# untitled.net
KiCad netlist of a schematic drawn in EAGLE
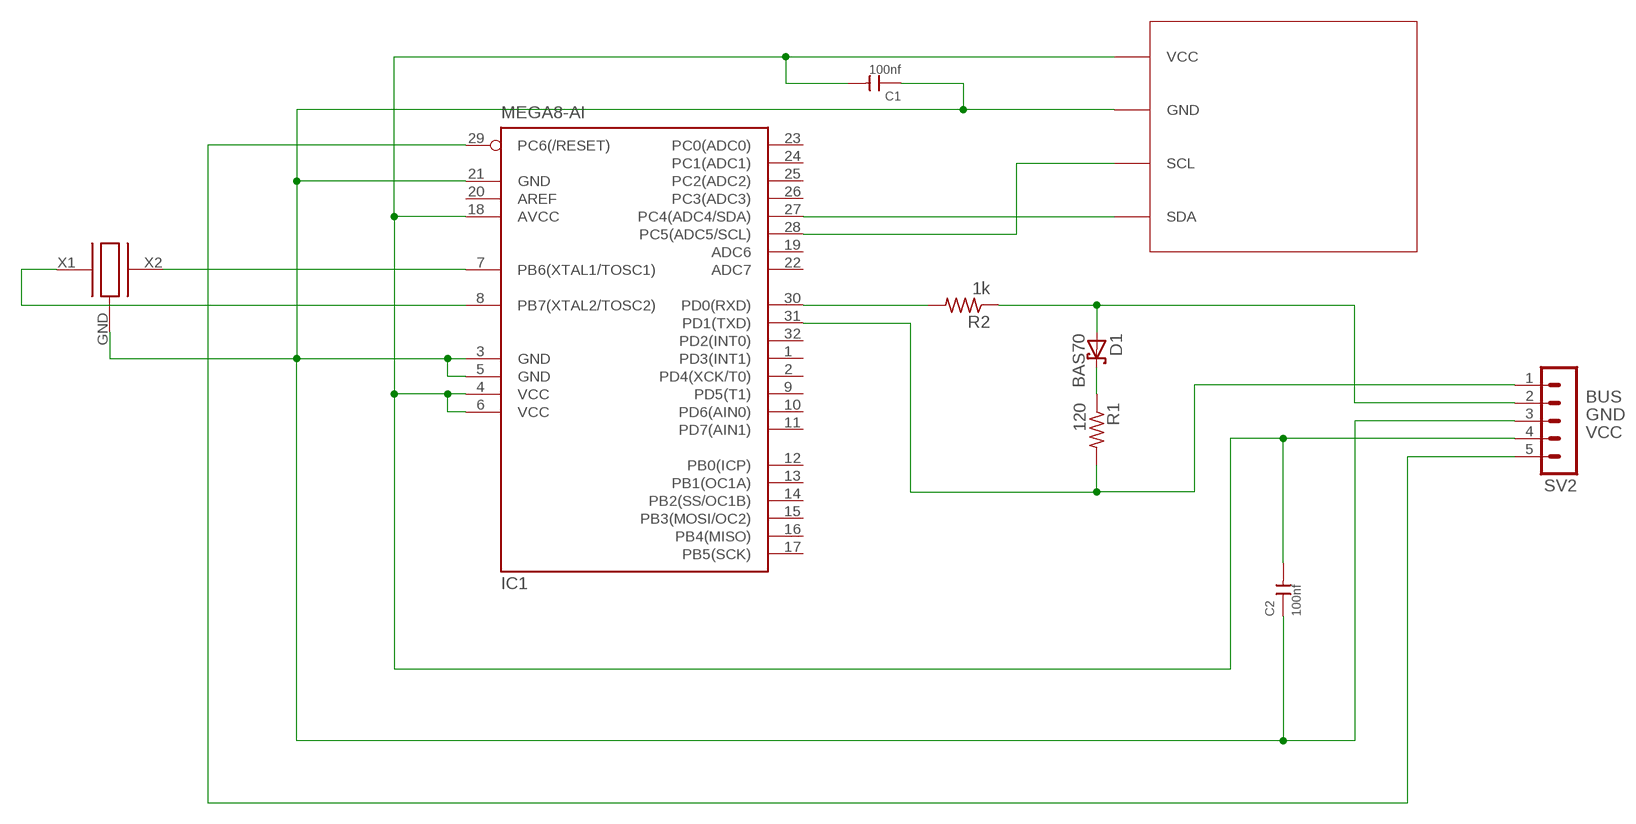
[diagram p0: schematic, sheet 1]

(export (version "E")
  (design (tool "Eeschema 10.0.6"))
  (components
    (comp (ref "C1")
      (value "100nf")
      (footprint "eagle-import:C0805")
      (fields (field (name "MPN") "CC0805JRX7R9BB103"))
      (libsource (lib "eagle-import") (part "CERAMIC-10NF-50V-5%-X7R(0805)"))
    )
    (comp (ref "C2")
      (value "100nf")
      (footprint "eagle-import:C0805")
      (fields (field (name "MPN") "CC0805JRX7R9BB103"))
      (libsource (lib "eagle-import") (part "CERAMIC-10NF-50V-5%-X7R(0805)"))
    )
    (comp (ref "D1")
      (value "BAS70")
      (footprint "eagle-import:SOT23")
      (libsource (lib "eagle-import") (part "BAS70"))
    )
    (comp (ref "IC1")
      (value "MEGA8-AI")
      (footprint "eagle-import:TQFP32-08")
      (fields (field (name "MPN") "ATMEGA8-16AU"))
      (libsource (lib "eagle-import") (part "MEGA8-AI"))
    )
    (comp (ref "R1")
      (value "120")
      (footprint "eagle-import:M0805")
      (libsource (lib "eagle-import") (part "R-US_M0805"))
    )
    (comp (ref "R2")
      (value "1k")
      (footprint "eagle-import:M0805")
      (libsource (lib "eagle-import") (part "R-US_M0805"))
    )
    (comp (ref "SV2")
      (value "MA05-1")
      (footprint "eagle-import:MA05-1")
      (libsource (lib "eagle-import") (part "MA05-1"))
    )
    (comp (ref "U$1")
      (value "AMOLED_ADAFRUIT")
      (footprint "eagle-import:AMOLED_PCB")
      (libsource (lib "eagle-import") (part "AMOLED_ADAFRUIT"))
    )
    (comp (ref "U$2")
      (value "MURATA_XTALL")
      (footprint "eagle-import:MURATA")
      (libsource (lib "eagle-import") (part "MURATA_XTALL"))
    )
  )
  (nets
    (net (code "1") (name "/BUS") (class "Default")
      (node (ref "D1") (pin "1") (pinfunction "A_1") (pintype "passive"))
      (node (ref "R2") (pin "1") (pinfunction "1_1") (pintype "passive"))
      (node (ref "SV2") (pin "2") (pinfunction "2_2") (pintype "passive"))
    )
    (net (code "2") (name "/GND") (class "Default")
      (node (ref "C1") (pin "1") (pinfunction "1_1") (pintype "passive"))
      (node (ref "C2") (pin "1") (pinfunction "1_1") (pintype "passive"))
      (node (ref "IC1") (pin "21") (pinfunction "GND_21") (pintype "power_in"))
      (node (ref "IC1") (pin "3") (pinfunction "GND_3") (pintype "power_in"))
      (node (ref "IC1") (pin "5") (pinfunction "GND_5") (pintype "power_in"))
      (node (ref "SV2") (pin "3") (pinfunction "3_3") (pintype "passive"))
      (node (ref "U$1") (pin "GND") (pinfunction "GND_GND") (pintype "power_in"))
      (node (ref "U$2") (pin "GND") (pinfunction "GND_GND") (pintype "input"))
    )
    (net (code "3") (name "/VCC") (class "Default")
      (node (ref "C1") (pin "2") (pinfunction "2_2") (pintype "passive"))
      (node (ref "C2") (pin "2") (pinfunction "2_2") (pintype "passive"))
      (node (ref "IC1") (pin "18") (pinfunction "AVCC_18") (pintype "power_in"))
      (node (ref "IC1") (pin "4") (pinfunction "VCC_4") (pintype "power_in"))
      (node (ref "IC1") (pin "6") (pinfunction "VCC_6") (pintype "power_in"))
      (node (ref "SV2") (pin "4") (pinfunction "4_4") (pintype "passive"))
      (node (ref "U$1") (pin "VCC") (pinfunction "VCC_VCC") (pintype "power_in"))
    )
    (net (code "4") (name "Net-(D1-C)") (class "Default")
      (node (ref "D1") (pin "3") (pinfunction "C_3") (pintype "passive"))
      (node (ref "R1") (pin "1") (pinfunction "1_1") (pintype "passive"))
    )
    (net (code "5") (name "Net-(IC1-PB6(XTAL1{slash}TOSC1))") (class "Default")
      (node (ref "IC1") (pin "7") (pinfunction "PB6(XTAL1/TOSC1)_7") (pintype "bidirectional"))
      (node (ref "U$2") (pin "X2") (pinfunction "X2_X2") (pintype "bidirectional"))
    )
    (net (code "6") (name "Net-(IC1-PB7(XTAL2{slash}TOSC2))") (class "Default")
      (node (ref "IC1") (pin "8") (pinfunction "PB7(XTAL2/TOSC2)_8") (pintype "bidirectional"))
      (node (ref "U$2") (pin "X1") (pinfunction "X1_X1") (pintype "bidirectional"))
    )
    (net (code "7") (name "Net-(IC1-PC4(ADC4{slash}SDA))") (class "Default")
      (node (ref "IC1") (pin "27") (pinfunction "PC4(ADC4/SDA)_27") (pintype "bidirectional"))
      (node (ref "U$1") (pin "SDA") (pinfunction "SDA_SDA") (pintype "input"))
    )
    (net (code "8") (name "Net-(IC1-PC5(ADC5{slash}SCL))") (class "Default")
      (node (ref "IC1") (pin "28") (pinfunction "PC5(ADC5/SCL)_28") (pintype "bidirectional"))
      (node (ref "U$1") (pin "SCL") (pinfunction "SCL_SCL") (pintype "input"))
    )
    (net (code "9") (name "Net-(IC1-PC6({slash}RESET))") (class "Default")
      (node (ref "IC1") (pin "29") (pinfunction "PC6(/RESET)_29") (pintype "bidirectional"))
      (node (ref "SV2") (pin "5") (pinfunction "5_5") (pintype "passive"))
    )
    (net (code "10") (name "Net-(IC1-PD0(RXD))") (class "Default")
      (node (ref "IC1") (pin "30") (pinfunction "PD0(RXD)_30") (pintype "bidirectional"))
      (node (ref "R2") (pin "2") (pinfunction "2_2") (pintype "passive"))
    )
    (net (code "11") (name "Net-(IC1-PD1(TXD))") (class "Default")
      (node (ref "IC1") (pin "31") (pinfunction "PD1(TXD)_31") (pintype "bidirectional"))
      (node (ref "R1") (pin "2") (pinfunction "2_2") (pintype "passive"))
      (node (ref "SV2") (pin "1") (pinfunction "1_1") (pintype "passive"))
    )
    (net (code "12") (name "unconnected-(IC1-ADC6-Pad19)") (class "Default")
      (node (ref "IC1") (pin "19") (pinfunction "ADC6_19") (pintype "bidirectional"))
    )
    (net (code "13") (name "unconnected-(IC1-ADC7-Pad22)") (class "Default")
      (node (ref "IC1") (pin "22") (pinfunction "ADC7_22") (pintype "bidirectional"))
    )
    (net (code "14") (name "unconnected-(IC1-AREF-Pad20)") (class "Default")
      (node (ref "IC1") (pin "20") (pinfunction "AREF_20") (pintype "passive"))
    )
    (net (code "15") (name "unconnected-(IC1-PB0(ICP)-Pad12)") (class "Default")
      (node (ref "IC1") (pin "12") (pinfunction "PB0(ICP)_12") (pintype "bidirectional"))
    )
    (net (code "16") (name "unconnected-(IC1-PB1(OC1A)-Pad13)") (class "Default")
      (node (ref "IC1") (pin "13") (pinfunction "PB1(OC1A)_13") (pintype "bidirectional"))
    )
    (net (code "17") (name "unconnected-(IC1-PB2(SS{slash}OC1B)-Pad14)") (class "Default")
      (node (ref "IC1") (pin "14") (pinfunction "PB2(SS/OC1B)_14") (pintype "bidirectional"))
    )
    (net (code "18") (name "unconnected-(IC1-PB3(MOSI{slash}OC2)-Pad15)") (class "Default")
      (node (ref "IC1") (pin "15") (pinfunction "PB3(MOSI/OC2)_15") (pintype "bidirectional"))
    )
    (net (code "19") (name "unconnected-(IC1-PB4(MISO)-Pad16)") (class "Default")
      (node (ref "IC1") (pin "16") (pinfunction "PB4(MISO)_16") (pintype "bidirectional"))
    )
    (net (code "20") (name "unconnected-(IC1-PB5(SCK)-Pad17)") (class "Default")
      (node (ref "IC1") (pin "17") (pinfunction "PB5(SCK)_17") (pintype "bidirectional"))
    )
    (net (code "21") (name "unconnected-(IC1-PC0(ADC0)-Pad23)") (class "Default")
      (node (ref "IC1") (pin "23") (pinfunction "PC0(ADC0)_23") (pintype "bidirectional"))
    )
    (net (code "22") (name "unconnected-(IC1-PC1(ADC1)-Pad24)") (class "Default")
      (node (ref "IC1") (pin "24") (pinfunction "PC1(ADC1)_24") (pintype "bidirectional"))
    )
    (net (code "23") (name "unconnected-(IC1-PC2(ADC2)-Pad25)") (class "Default")
      (node (ref "IC1") (pin "25") (pinfunction "PC2(ADC2)_25") (pintype "bidirectional"))
    )
    (net (code "24") (name "unconnected-(IC1-PC3(ADC3)-Pad26)") (class "Default")
      (node (ref "IC1") (pin "26") (pinfunction "PC3(ADC3)_26") (pintype "bidirectional"))
    )
    (net (code "25") (name "unconnected-(IC1-PD2(INT0)-Pad32)") (class "Default")
      (node (ref "IC1") (pin "32") (pinfunction "PD2(INT0)_32") (pintype "bidirectional"))
    )
    (net (code "26") (name "unconnected-(IC1-PD3(INT1)-Pad1)") (class "Default")
      (node (ref "IC1") (pin "1") (pinfunction "PD3(INT1)_1") (pintype "bidirectional"))
    )
    (net (code "27") (name "unconnected-(IC1-PD4(XCK{slash}T0)-Pad2)") (class "Default")
      (node (ref "IC1") (pin "2") (pinfunction "PD4(XCK/T0)_2") (pintype "bidirectional"))
    )
    (net (code "28") (name "unconnected-(IC1-PD5(T1)-Pad9)") (class "Default")
      (node (ref "IC1") (pin "9") (pinfunction "PD5(T1)_9") (pintype "bidirectional"))
    )
    (net (code "29") (name "unconnected-(IC1-PD6(AIN0)-Pad10)") (class "Default")
      (node (ref "IC1") (pin "10") (pinfunction "PD6(AIN0)_10") (pintype "bidirectional"))
    )
    (net (code "30") (name "unconnected-(IC1-PD7(AIN1)-Pad11)") (class "Default")
      (node (ref "IC1") (pin "11") (pinfunction "PD7(AIN1)_11") (pintype "bidirectional"))
    )
  )
)
